# Ada.net
KiCad netlist of a schematic drawn in EasyEDA Pro
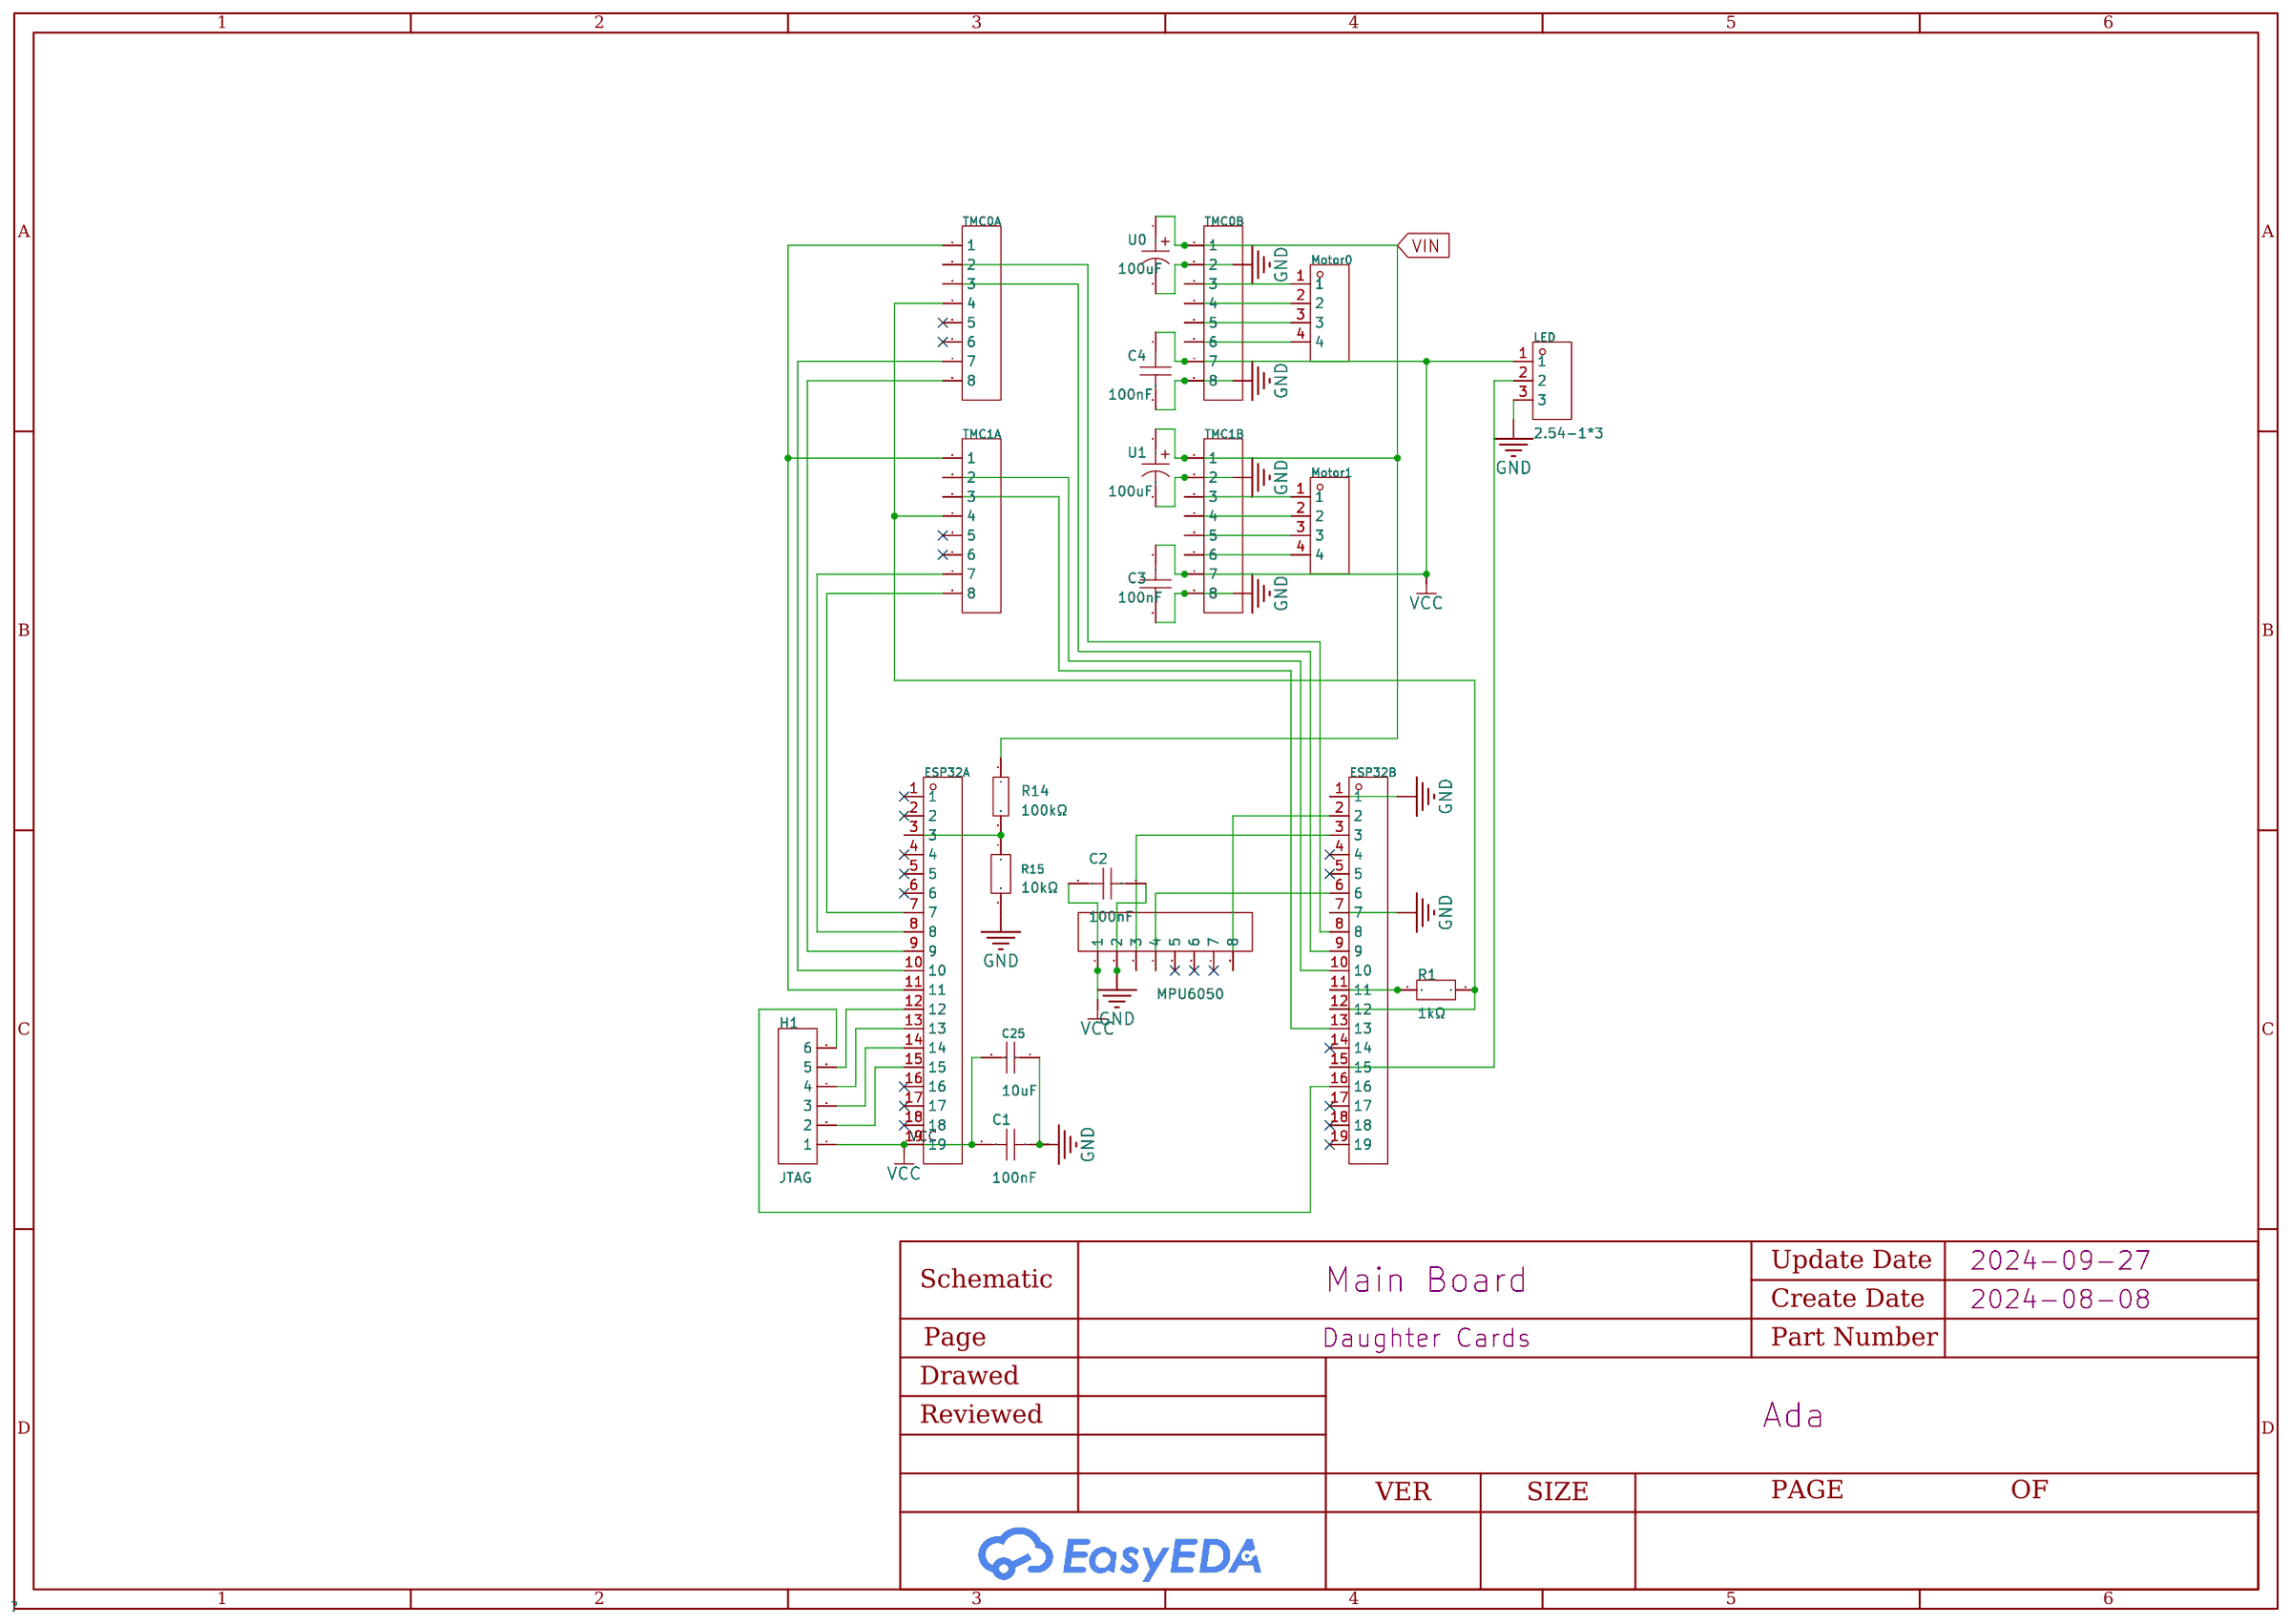
[diagram p0: Daughter Cards]
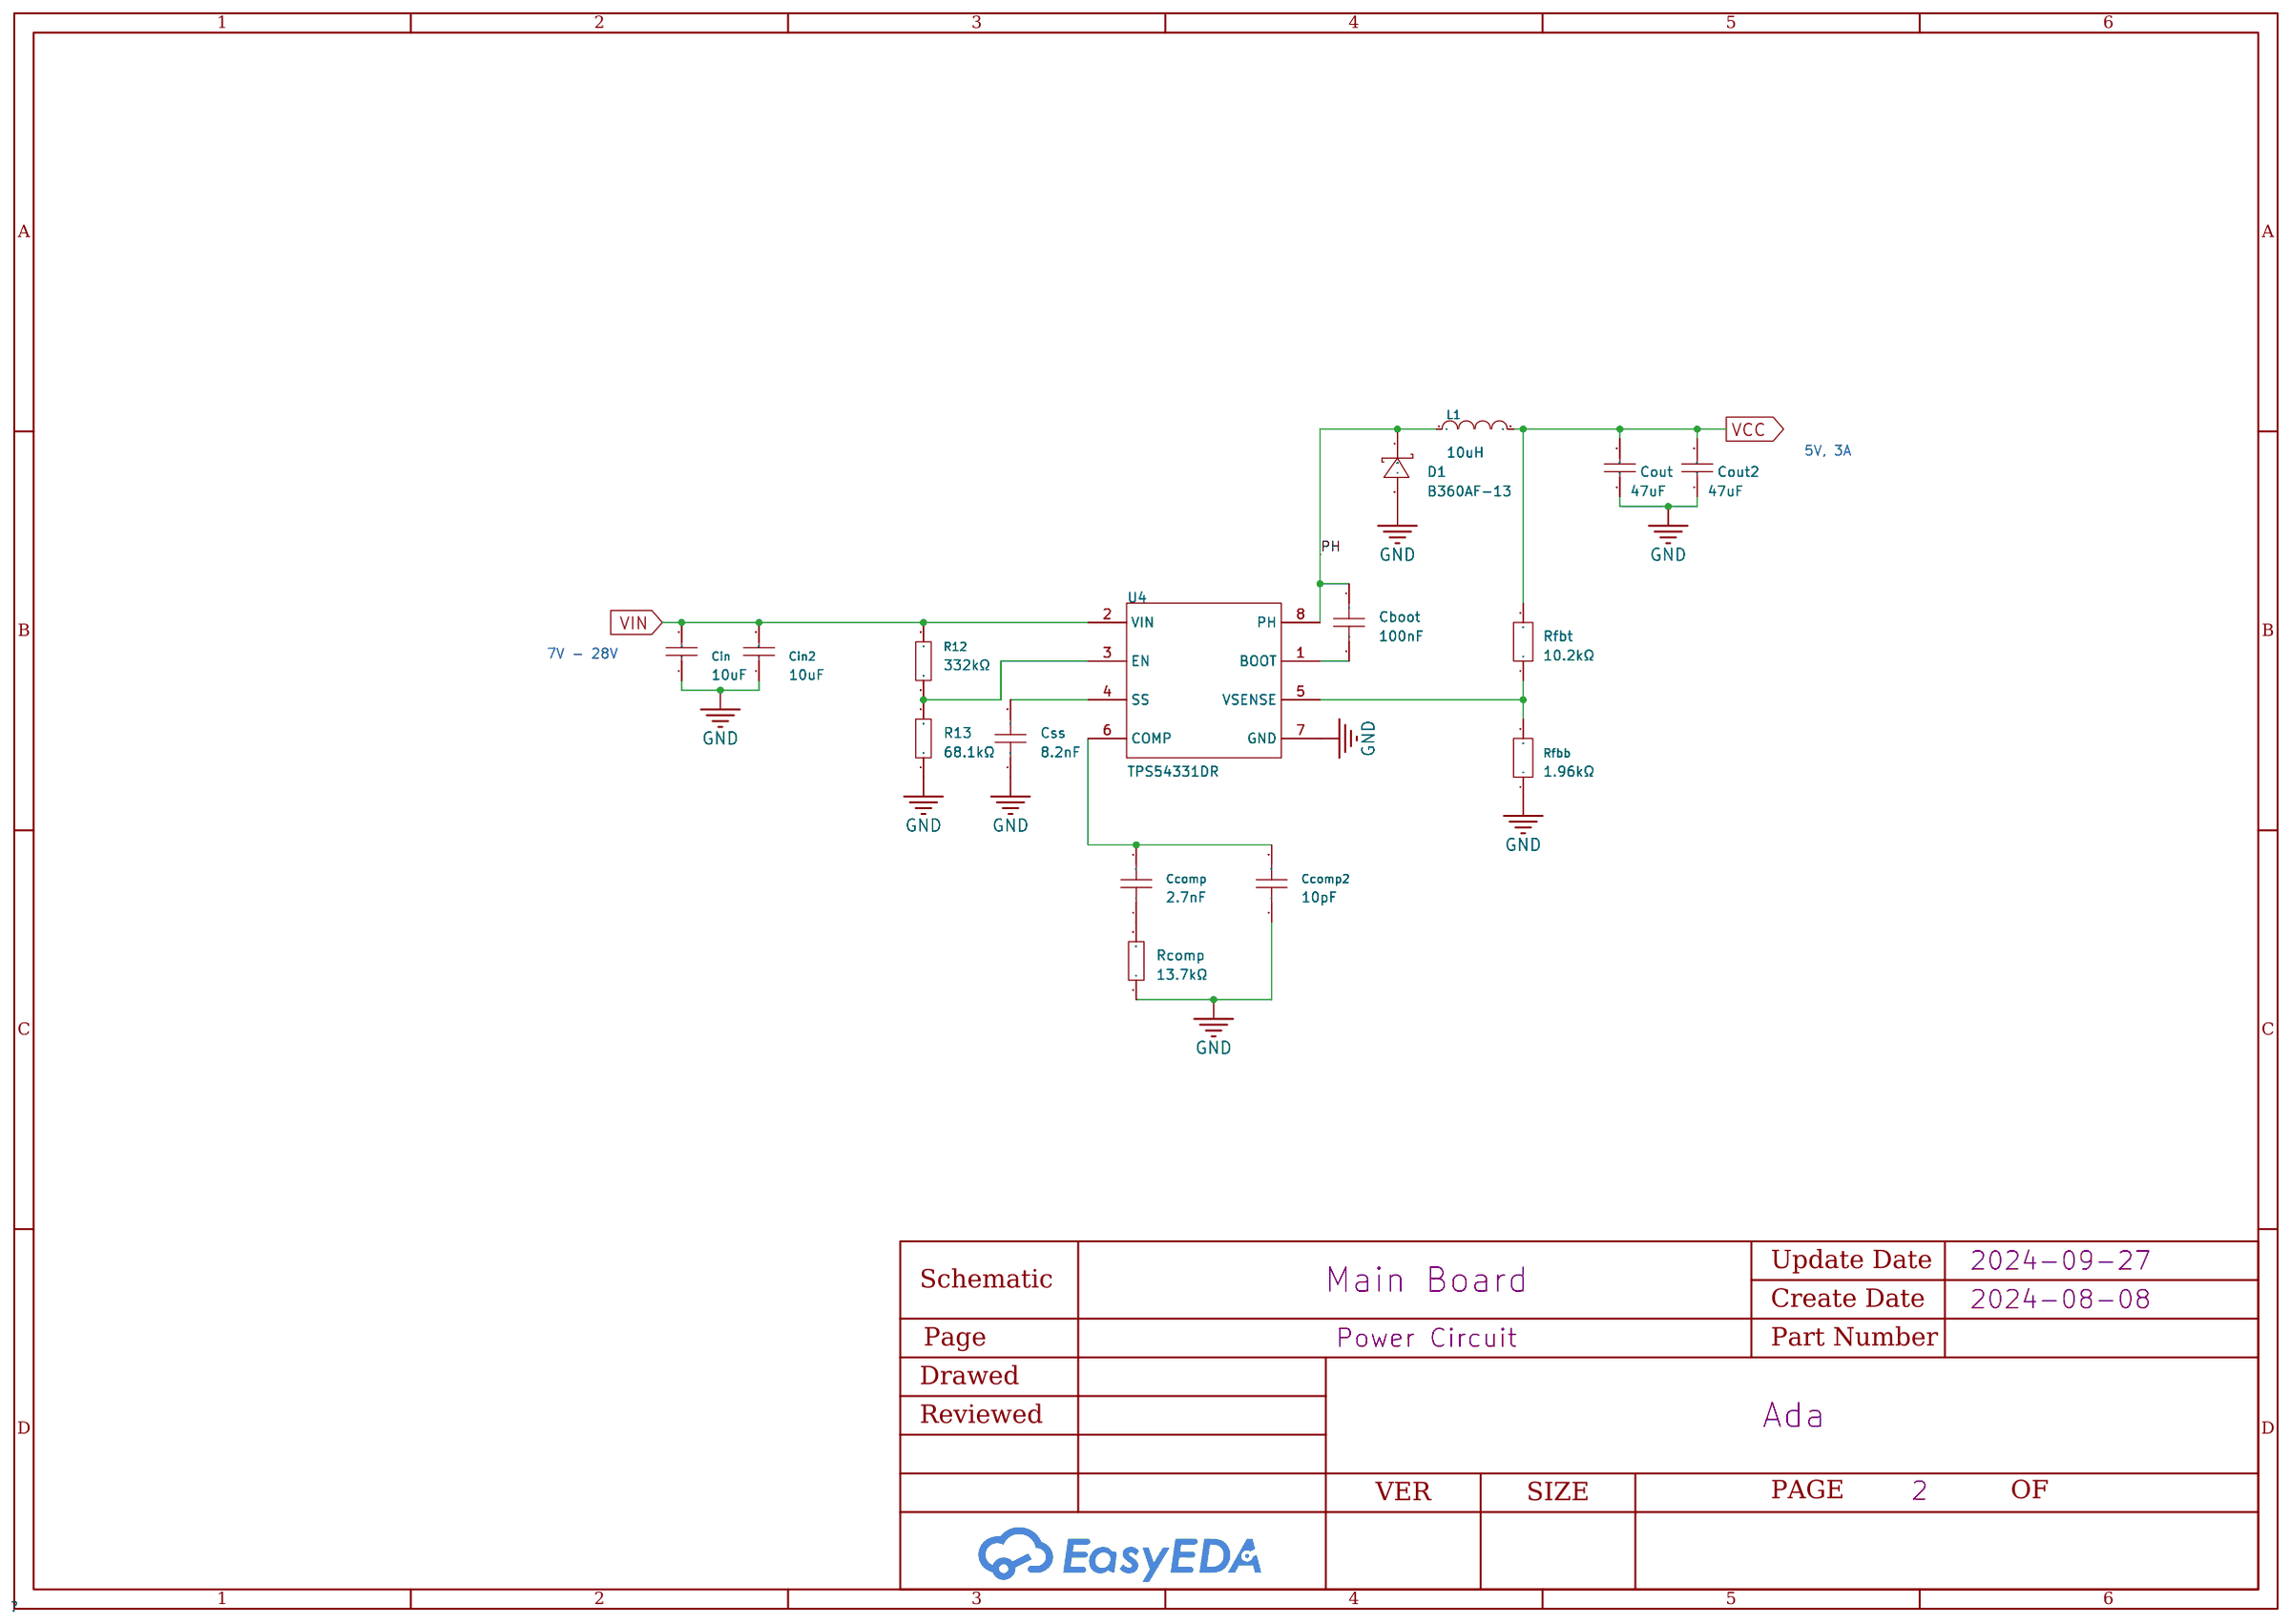
[diagram p1: Power Circuit]
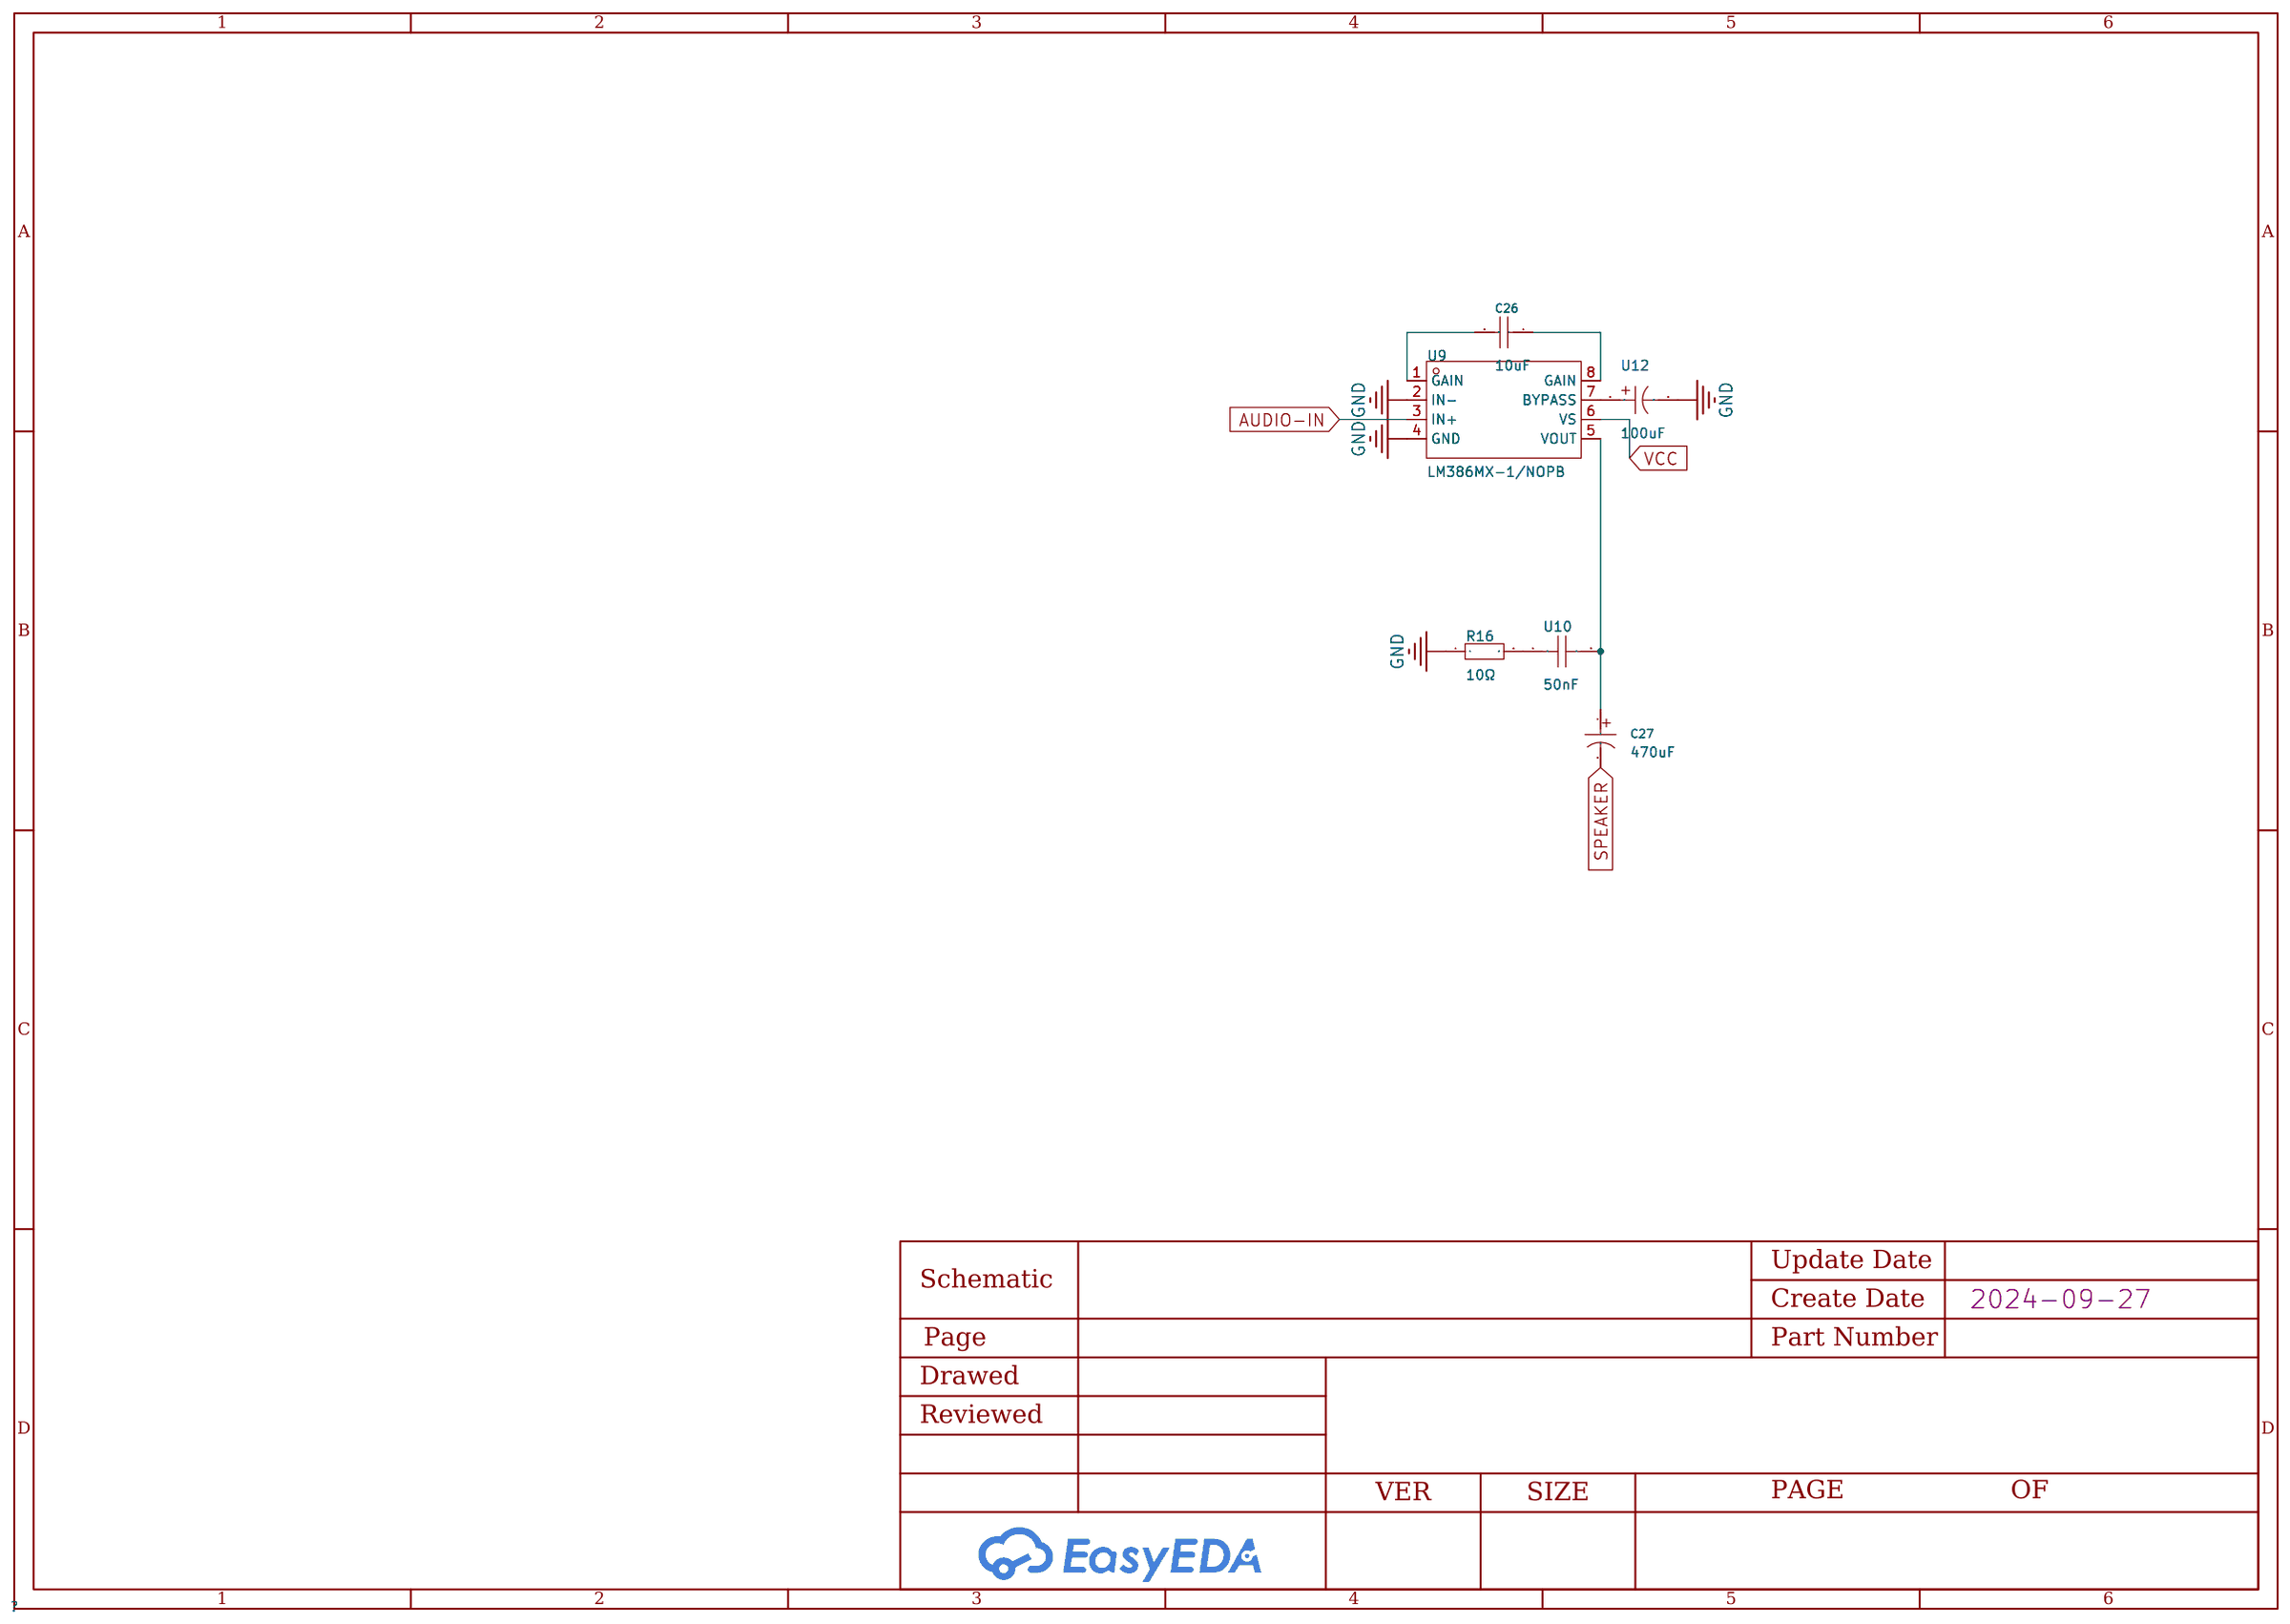
[diagram p2: Audio Amplifier]

(export (version "E")
  (design (tool "Eeschema 10.0.6"))
  (components
    (comp (ref "C1")
      (value "100nF")
      (footprint "easyedapro:C0201")
      (fields
        (field (name "Manufacturer Part") "CL03A104KQ3NNNC")
        (field (name "Manufacturer") "SAMSUNG(三星)")
      )
      (libsource (lib "easyedapro") (part "CL03A104KQ3NNNC"))
    )
    (comp (ref "C2")
      (value "100nF")
      (footprint "easyedapro:C0201")
      (fields
        (field (name "Manufacturer Part") "CL03A104KQ3NNNC")
        (field (name "Manufacturer") "SAMSUNG(三星)")
      )
      (libsource (lib "easyedapro") (part "CL03A104KQ3NNNC"))
    )
    (comp (ref "C3")
      (value "100nF")
      (footprint "easyedapro:C0201")
      (fields
        (field (name "Manufacturer Part") "CL03A104KQ3NNNC")
        (field (name "Manufacturer") "SAMSUNG(三星)")
      )
      (libsource (lib "easyedapro") (part "CL03A104KQ3NNNC"))
    )
    (comp (ref "C4")
      (value "100nF")
      (footprint "easyedapro:C0201")
      (fields
        (field (name "Manufacturer Part") "CL03A104KQ3NNNC")
        (field (name "Manufacturer") "SAMSUNG(三星)")
      )
      (libsource (lib "easyedapro") (part "CL03A104KQ3NNNC"))
    )
    (comp (ref "C25")
      (value "10uF")
      (footprint "easyedapro:C0402")
      (fields
        (field (name "Manufacturer Part") "CL05A106MQ5NUNC")
        (field (name "Manufacturer") "SAMSUNG(三星)")
      )
      (libsource (lib "easyedapro") (part "CL05A106MQ5NUNC"))
    )
    (comp (ref "ESP32A")
      (value "ESP32")
      (footprint "easyedapro:HDR-TH_19P-P2.54-V-F")
      (fields (field (name "Manufacturer Part") "2.54-1*19P母") (field (name "Manufacturer") "BOOMELE(博穆精密)"))
      (libsource (lib "easyedapro") (part "2.54-1*19P母"))
    )
    (comp (ref "ESP32B")
      (value "2.54-1*19P母")
      (footprint "easyedapro:HDR-TH_19P-P2.54-V-F")
      (fields (field (name "Manufacturer") "BOOMELE(博穆精密)"))
      (libsource (lib "easyedapro") (part "2.54-1*19P母"))
    )
    (comp (ref "H1")
      (value "JTAG")
      (footprint "easyedapro:HDR-TH_6P-P2.54-V-M-1")
      (fields (field (name "Manufacturer Part") "2.54-1x6P直针") (field (name "Manufacturer") "BOOMELE(博穆精密)"))
      (libsource (lib "easyedapro") (part "Header-Male-2.54_1x6"))
    )
    (comp (ref "LED")
      (value "2.54-1*3")
      (footprint "easyedapro:HDR-TH_3P-P2.54-V-M-1")
      (description "Pin Structure:1x3P Pitch:2.54mm Number of Rows:Plugin Number of Pins:3P Contact Plating:Gold")
      (fields (field (name "Manufacturer") "ZHOURI(洲日)"))
      (libsource (lib "easyedapro") (part "2.54-1*3"))
    )
    (comp (ref "Motor0")
      (value "Motor 0")
      (footprint "easyedapro:HDR-TH_4P-P2.54-V-M")
      (fields (field (name "Manufacturer Part") "PZ254V-11-04P") (field (name "Manufacturer") "XFCN(兴飞)"))
      (libsource (lib "easyedapro") (part "PZ254V-11-04P_C2691448"))
    )
    (comp (ref "Motor1")
      (value "Motor 1")
      (footprint "easyedapro:HDR-TH_4P-P2.54-V-M")
      (fields (field (name "Manufacturer Part") "PZ254V-11-04P") (field (name "Manufacturer") "XFCN(兴飞)"))
      (libsource (lib "easyedapro") (part "PZ254V-11-04P_C2691448"))
    )
    (comp (ref "MPU6050")
      (value "MPU6050")
      (footprint "easyedapro:HDR-TH_8P-P2.54-V-F-1")
      (fields (field (name "Manufacturer Part") "2.54-1*8P母环保") (field (name "Manufacturer") "BOOMELE(博穆精密)"))
      (libsource (lib "easyedapro") (part "Header-Female-2.54_1x8"))
    )
    (comp (ref "R1")
      (value "1kΩ")
      (footprint "easyedapro:R0603")
      (fields (field (name "Manufacturer Part") "FCR0603F1K") (field (name "Manufacturer") "VO(翔胜)"))
      (libsource (lib "easyedapro") (part "FCR0603F1K"))
    )
    (comp (ref "R14")
      (value "100kΩ")
      (footprint "easyedapro:R0201")
      (fields
        (field (name "Manufacturer Part") "0201WMF1003TEE")
        (field (name "Manufacturer") "UNI-ROYAL(厚声)")
      )
      (libsource (lib "easyedapro") (part "0201WMF1003TEE"))
    )
    (comp (ref "R15")
      (value "10kΩ")
      (footprint "easyedapro:R0201")
      (fields
        (field (name "Manufacturer Part") "0201WMF1002TEE")
        (field (name "Manufacturer") "UNI-ROYAL(厚声)")
      )
      (libsource (lib "easyedapro") (part "0201WMF1002TEE"))
    )
    (comp (ref "TMC0A")
      (value "TMC0A")
      (footprint "easyedapro:HDR-TH_8P-P2.54-V-F-1")
      (fields (field (name "Manufacturer Part") "2.54-1*8P母环保") (field (name "Manufacturer") "BOOMELE(博穆精密)"))
      (libsource (lib "easyedapro") (part "Header-Female-2.54_1x8"))
    )
    (comp (ref "TMC0B")
      (value "2.54-1*8P母环保")
      (footprint "easyedapro:HDR-TH_8P-P2.54-V-F-1")
      (fields (field (name "Manufacturer") "BOOMELE(博穆精密)"))
      (libsource (lib "easyedapro") (part "Header-Female-2.54_1x8"))
    )
    (comp (ref "TMC1A")
      (value "TMC2209")
      (footprint "easyedapro:HDR-TH_8P-P2.54-V-F-1")
      (fields (field (name "Manufacturer Part") "2.54-1*8P母环保") (field (name "Manufacturer") "BOOMELE(博穆精密)"))
      (libsource (lib "easyedapro") (part "Header-Female-2.54_1x8"))
    )
    (comp (ref "TMC1B")
      (value "2.54-1*8P母环保")
      (footprint "easyedapro:HDR-TH_8P-P2.54-V-F-1")
      (fields (field (name "Manufacturer") "BOOMELE(博穆精密)"))
      (libsource (lib "easyedapro") (part "Header-Female-2.54_1x8"))
    )
    (comp (ref "U0")
      (value "100uF")
      (footprint "easyedapro:CAP-TH_BD6.3-P2.50-D0.5-FD")
      (fields (field (name "Manufacturer Part") "03EC0728") (field (name "Manufacturer") "KNSCHA(科尼盛)"))
      (libsource (lib "easyedapro") (part "03EC0728"))
    )
    (comp (ref "U1")
      (value "100uF")
      (footprint "easyedapro:CAP-TH_BD6.3-P2.50-D0.5-FD")
      (fields (field (name "Manufacturer Part") "03EC0728") (field (name "Manufacturer") "KNSCHA(科尼盛)"))
      (libsource (lib "easyedapro") (part "03EC0728"))
    )
    (comp (ref "Cboot")
      (value "100nF")
      (footprint "easyedapro:C0201")
      (fields
        (field (name "Manufacturer Part") "CL03A104KQ3NNNC")
        (field (name "Manufacturer") "SAMSUNG(三星)")
      )
      (libsource (lib "easyedapro") (part "CL03A104KQ3NNNC"))
    )
    (comp (ref "Ccomp")
      (value "2.7nF")
      (footprint "easyedapro:C0402")
      (fields
        (field (name "Manufacturer Part") "CC0402KRX7R8BB272")
        (field (name "Manufacturer") "YAGEO(国巨)")
      )
      (libsource (lib "easyedapro") (part "CC0402KRX7R8BB272"))
    )
    (comp (ref "Ccomp2")
      (value "10pF")
      (footprint "easyedapro:C0402")
      (fields (field (name "Manufacturer Part") "0402N100J250CT") (field (name "Manufacturer") "Walsin(华新科)"))
      (libsource (lib "easyedapro") (part "0402N100J250CT"))
    )
    (comp (ref "Cin")
      (value "10uF")
      (footprint "easyedapro:C1206")
      (fields
        (field (name "Manufacturer Part") "CL31A106KAHNNNE")
        (field (name "Manufacturer") "SAMSUNG(三星)")
      )
      (libsource (lib "easyedapro") (part "CL31A106KAHNNNE"))
    )
    (comp (ref "Cin2")
      (value "10uF")
      (footprint "easyedapro:C1206")
      (fields
        (field (name "Manufacturer Part") "CL31A106KAHNNNE")
        (field (name "Manufacturer") "SAMSUNG(三星)")
      )
      (libsource (lib "easyedapro") (part "CL31A106KAHNNNE"))
    )
    (comp (ref "Cout")
      (value "47uF")
      (footprint "easyedapro:C0805")
      (fields
        (field (name "Manufacturer Part") "CL21A476MQYNNNE")
        (field (name "Manufacturer") "SAMSUNG(三星)")
      )
      (libsource (lib "easyedapro") (part "CL21A476MQYNNNE"))
    )
    (comp (ref "Cout2")
      (value "47uF")
      (footprint "easyedapro:C0805")
      (fields
        (field (name "Manufacturer Part") "CL21A476MQYNNNE")
        (field (name "Manufacturer") "SAMSUNG(三星)")
      )
      (libsource (lib "easyedapro") (part "CL21A476MQYNNNE"))
    )
    (comp (ref "Css")
      (value "8.2nF")
      (footprint "easyedapro:C0201")
      (fields (field (name "Manufacturer Part") "C0603X7R822KDTS") (field (name "Manufacturer") "DARFON(达方)"))
      (libsource (lib "easyedapro") (part "C0603X7R822KDTS"))
    )
    (comp (ref "D1")
      (value "B360AF-13")
      (footprint "easyedapro:SMA_L4.4-W2.6-LS5.0-RD")
      (fields (field (name "Manufacturer") "DIODES(美台)"))
      (libsource (lib "easyedapro") (part "B360AF-13"))
    )
    (comp (ref "L1")
      (value "10uH")
      (footprint "easyedapro:IND-SMD_L7.2-W6.6_GPSR07X0")
      (fields (field (name "Manufacturer Part") "CYA0630-10UH") (field (name "Manufacturer") "SHOU HAN(首韩)"))
      (libsource (lib "easyedapro") (part "CYA0630-10UH"))
    )
    (comp (ref "R12")
      (value "332kΩ")
      (footprint "easyedapro:R0402")
      (fields
        (field (name "Manufacturer Part") "0402WGF3323TCE")
        (field (name "Manufacturer") "UNI-ROYAL(厚声)")
      )
      (libsource (lib "easyedapro") (part "0402WGF3323TCE"))
    )
    (comp (ref "R13")
      (value "68.1kΩ")
      (footprint "easyedapro:R0402")
      (fields (field (name "Manufacturer Part") "AC0402FR-0768K1L") (field (name "Manufacturer") "YAGEO(国巨)"))
      (libsource (lib "easyedapro") (part "AC0402FR-0768K1L"))
    )
    (comp (ref "Rcomp")
      (value "13.7kΩ")
      (footprint "easyedapro:R0201")
      (fields (field (name "Manufacturer Part") "RC-01W1372FT") (field (name "Manufacturer") "FH(风华)"))
      (libsource (lib "easyedapro") (part "RC-01W1372FT"))
    )
    (comp (ref "Rfbb")
      (value "1.96kΩ")
      (footprint "easyedapro:R0201")
      (fields
        (field (name "Manufacturer Part") "0201WMF1961TEE")
        (field (name "Manufacturer") "UNI-ROYAL(厚声)")
      )
      (libsource (lib "easyedapro") (part "0201WMF1961TEE"))
    )
    (comp (ref "Rfbt")
      (value "10.2kΩ")
      (footprint "easyedapro:R0201")
      (fields (field (name "Manufacturer Part") "RTT011022FTH") (field (name "Manufacturer") "RALEC(旺诠)"))
      (libsource (lib "easyedapro") (part "RTT011022FTH"))
    )
    (comp (ref "U4")
      (value "TPS54331DR")
      (footprint "easyedapro:SOIC-8_L5.0-W4.0-P1.27-LS6.0-BL")
      (fields (field (name "Manufacturer") "TI(德州仪器)"))
      (libsource (lib "easyedapro") (part "TPS54331DR"))
    )
    (comp (ref "C26")
      (value "10uF")
      (footprint "easyedapro:C0402")
      (fields
        (field (name "Manufacturer Part") "CL05A106MQ5NUNC")
        (field (name "Manufacturer") "SAMSUNG(三星)")
      )
      (libsource (lib "easyedapro") (part "CL05A106MQ5NUNC"))
    )
    (comp (ref "C27")
      (value "470uF")
      (footprint "easyedapro:CAP-TH_BD8.0-P3.50-D0.6-FD")
      (fields
        (field (name "Manufacturer Part") "KM477M016F12RR0VH2FP0")
        (field (name "Manufacturer") "CX(承兴)")
      )
      (libsource (lib "easyedapro") (part "470uf16v"))
    )
    (comp (ref "R16")
      (value "10Ω")
      (footprint "easyedapro:R01005")
      (fields (field (name "Manufacturer Part") "MCR004YZPJ100") (field (name "Manufacturer") "ROHM(罗姆)"))
      (libsource (lib "easyedapro") (part "MCR004YZPJ100"))
    )
    (comp (ref "U9")
      (value "LM386MX-1/NOPB")
      (footprint "easyedapro:SOIC-8_L4.9-W3.9-P1.27-LS6.0-BL")
      (fields (field (name "Manufacturer") "TI(德州仪器)"))
      (libsource (lib "easyedapro") (part "LM386MX-1/NOPB"))
    )
    (comp (ref "U10")
      (value "50nF")
      (footprint "easyedapro:C1206")
      (fields (field (name "Manufacturer Part") "12065C503JAT2A") (field (name "Manufacturer") "Kyocera AVX"))
      (libsource (lib "easyedapro") (part "12065C503JAT2A"))
    )
    (comp (ref "U12")
      (value "100uF")
      (footprint "easyedapro:CAP-TH_BD6.3-P2.50-D0.5-FD")
      (fields (field (name "Manufacturer Part") "03EC0728") (field (name "Manufacturer") "KNSCHA(科尼盛)"))
      (libsource (lib "easyedapro") (part "03EC0728"))
    )
  )
  (nets
    (net (code "1") (name "AUDIO-IN") (class "Default")
      (node (ref "U9") (pin "3") (pinfunction "IN+_3") (pintype "input"))
    )
    (net (code "2") (name "GND") (class "Default")
      (node (ref "C1") (pin "2") (pinfunction "2_2") (pintype "unspecified"))
      (node (ref "C2") (pin "2") (pinfunction "2_2") (pintype "unspecified"))
      (node (ref "C25") (pin "1") (pinfunction "1_1") (pintype "input"))
      (node (ref "C3") (pin "2") (pinfunction "2_2") (pintype "unspecified"))
      (node (ref "C4") (pin "2") (pinfunction "2_2") (pintype "unspecified"))
      (node (ref "Ccomp2") (pin "1") (pinfunction "1_1") (pintype "input"))
      (node (ref "Cin") (pin "1") (pinfunction "1_1") (pintype "input"))
      (node (ref "Cin2") (pin "1") (pinfunction "1_1") (pintype "input"))
      (node (ref "Cout") (pin "1") (pinfunction "1_1") (pintype "input"))
      (node (ref "Cout2") (pin "1") (pinfunction "1_1") (pintype "input"))
      (node (ref "Css") (pin "1") (pinfunction "1_1") (pintype "unspecified"))
      (node (ref "D1") (pin "2") (pinfunction "A_2") (pintype "unspecified"))
      (node (ref "ESP32B") (pin "1") (pinfunction "1_1") (pintype "input"))
      (node (ref "ESP32B") (pin "7") (pinfunction "7_7") (pintype "input"))
      (node (ref "LED") (pin "3") (pinfunction "3_3") (pintype "input"))
      (node (ref "MPU6050") (pin "2") (pinfunction "2_2") (pintype "input"))
      (node (ref "R13") (pin "1") (pinfunction "1_1") (pintype "unspecified"))
      (node (ref "R15") (pin "2") (pinfunction "2_2") (pintype "input"))
      (node (ref "R16") (pin "1") (pinfunction "1_1") (pintype "input"))
      (node (ref "Rcomp") (pin "1") (pinfunction "1_1") (pintype "unspecified"))
      (node (ref "Rfbb") (pin "1") (pinfunction "1_1") (pintype "input"))
      (node (ref "TMC0B") (pin "2") (pinfunction "2_2") (pintype "input"))
      (node (ref "TMC0B") (pin "8") (pinfunction "8_8") (pintype "input"))
      (node (ref "TMC1B") (pin "2") (pinfunction "2_2") (pintype "input"))
      (node (ref "TMC1B") (pin "8") (pinfunction "8_8") (pintype "input"))
      (node (ref "U0") (pin "2") (pinfunction "2_2") (pintype "input"))
      (node (ref "U1") (pin "2") (pinfunction "2_2") (pintype "input"))
      (node (ref "U12") (pin "2") (pinfunction "2_2") (pintype "input"))
      (node (ref "U4") (pin "7") (pinfunction "GND_7") (pintype "unspecified"))
      (node (ref "U9") (pin "2") (pinfunction "IN-_2") (pintype "input"))
      (node (ref "U9") (pin "4") (pinfunction "GND_4") (pintype "input"))
    )
    (net (code "3") (name "Net-(C26-Pad1)") (class "Default")
      (node (ref "C26") (pin "1") (pinfunction "1_1") (pintype "input"))
      (node (ref "U9") (pin "8") (pinfunction "GAIN_8") (pintype "input"))
    )
    (net (code "4") (name "Net-(C26-Pad2)") (class "Default")
      (node (ref "C26") (pin "2") (pinfunction "2_2") (pintype "input"))
      (node (ref "U9") (pin "1") (pinfunction "GAIN_1") (pintype "input"))
    )
    (net (code "5") (name "Net-(Ccomp-Pad1)") (class "Default")
      (node (ref "Ccomp") (pin "1") (pinfunction "1_1") (pintype "input"))
      (node (ref "Rcomp") (pin "2") (pinfunction "2_2") (pintype "unspecified"))
    )
    (net (code "6") (name "Net-(ESP32A-Pad3)") (class "Default")
      (node (ref "ESP32A") (pin "3") (pinfunction "3_3") (pintype "input"))
      (node (ref "R14") (pin "2") (pinfunction "2_2") (pintype "unspecified"))
      (node (ref "R15") (pin "1") (pinfunction "1_1") (pintype "input"))
    )
    (net (code "7") (name "Net-(ESP32A-Pad7)") (class "Default")
      (node (ref "ESP32A") (pin "7") (pinfunction "7_7") (pintype "input"))
      (node (ref "TMC1A") (pin "8") (pinfunction "8_8") (pintype "input"))
    )
    (net (code "8") (name "Net-(ESP32A-Pad8)") (class "Default")
      (node (ref "ESP32A") (pin "8") (pinfunction "8_8") (pintype "input"))
      (node (ref "TMC1A") (pin "7") (pinfunction "7_7") (pintype "input"))
    )
    (net (code "9") (name "Net-(ESP32A-Pad9)") (class "Default")
      (node (ref "ESP32A") (pin "9") (pinfunction "9_9") (pintype "input"))
      (node (ref "TMC0A") (pin "8") (pinfunction "8_8") (pintype "input"))
    )
    (net (code "10") (name "Net-(ESP32A-Pad10)") (class "Default")
      (node (ref "ESP32A") (pin "10") (pinfunction "10_10") (pintype "input"))
      (node (ref "TMC0A") (pin "7") (pinfunction "7_7") (pintype "input"))
    )
    (net (code "11") (name "Net-(ESP32A-Pad11)") (class "Default")
      (node (ref "ESP32A") (pin "11") (pinfunction "11_11") (pintype "input"))
      (node (ref "TMC0A") (pin "1") (pinfunction "1_1") (pintype "input"))
      (node (ref "TMC1A") (pin "1") (pinfunction "1_1") (pintype "input"))
    )
    (net (code "12") (name "Net-(ESP32A-Pad12)") (class "Default")
      (node (ref "ESP32A") (pin "12") (pinfunction "12_12") (pintype "input"))
      (node (ref "H1") (pin "5") (pinfunction "5_5") (pintype "input"))
    )
    (net (code "13") (name "Net-(ESP32A-Pad13)") (class "Default")
      (node (ref "ESP32A") (pin "13") (pinfunction "13_13") (pintype "input"))
      (node (ref "H1") (pin "4") (pinfunction "4_4") (pintype "input"))
    )
    (net (code "14") (name "Net-(ESP32A-Pad14)") (class "Default")
      (node (ref "ESP32A") (pin "14") (pinfunction "14_14") (pintype "input"))
      (node (ref "H1") (pin "3") (pinfunction "3_3") (pintype "input"))
    )
    (net (code "15") (name "Net-(ESP32A-Pad15)") (class "Default")
      (node (ref "ESP32A") (pin "15") (pinfunction "15_15") (pintype "input"))
      (node (ref "H1") (pin "2") (pinfunction "2_2") (pintype "input"))
    )
    (net (code "16") (name "Net-(ESP32B-Pad2)") (class "Default")
      (node (ref "ESP32B") (pin "2") (pinfunction "2_2") (pintype "input"))
      (node (ref "MPU6050") (pin "8") (pinfunction "8_8") (pintype "input"))
    )
    (net (code "17") (name "Net-(ESP32B-Pad3)") (class "Default")
      (node (ref "ESP32B") (pin "3") (pinfunction "3_3") (pintype "input"))
      (node (ref "MPU6050") (pin "3") (pinfunction "3_3") (pintype "input"))
    )
    (net (code "18") (name "Net-(ESP32B-Pad6)") (class "Default")
      (node (ref "ESP32B") (pin "6") (pinfunction "6_6") (pintype "input"))
      (node (ref "MPU6050") (pin "4") (pinfunction "4_4") (pintype "input"))
    )
    (net (code "19") (name "Net-(ESP32B-Pad8)") (class "Default")
      (node (ref "ESP32B") (pin "8") (pinfunction "8_8") (pintype "input"))
      (node (ref "TMC0A") (pin "2") (pinfunction "2_2") (pintype "input"))
    )
    (net (code "20") (name "Net-(ESP32B-Pad9)") (class "Default")
      (node (ref "ESP32B") (pin "9") (pinfunction "9_9") (pintype "input"))
      (node (ref "TMC0A") (pin "3") (pinfunction "3_3") (pintype "input"))
    )
    (net (code "21") (name "Net-(ESP32B-Pad10)") (class "Default")
      (node (ref "ESP32B") (pin "10") (pinfunction "10_10") (pintype "input"))
      (node (ref "TMC1A") (pin "2") (pinfunction "2_2") (pintype "input"))
    )
    (net (code "22") (name "Net-(ESP32B-Pad11)") (class "Default")
      (node (ref "ESP32B") (pin "11") (pinfunction "11_11") (pintype "input"))
      (node (ref "R1") (pin "1") (pinfunction "1_1") (pintype "unspecified"))
    )
    (net (code "23") (name "Net-(ESP32B-Pad12)") (class "Default")
      (node (ref "ESP32B") (pin "12") (pinfunction "12_12") (pintype "input"))
      (node (ref "R1") (pin "2") (pinfunction "2_2") (pintype "unspecified"))
      (node (ref "TMC0A") (pin "4") (pinfunction "4_4") (pintype "input"))
      (node (ref "TMC1A") (pin "4") (pinfunction "4_4") (pintype "input"))
    )
    (net (code "24") (name "Net-(ESP32B-Pad13)") (class "Default")
      (node (ref "ESP32B") (pin "13") (pinfunction "13_13") (pintype "input"))
      (node (ref "TMC1A") (pin "3") (pinfunction "3_3") (pintype "input"))
    )
    (net (code "25") (name "Net-(ESP32B-Pad15)") (class "Default")
      (node (ref "ESP32B") (pin "15") (pinfunction "15_15") (pintype "input"))
      (node (ref "LED") (pin "2") (pinfunction "2_2") (pintype "input"))
    )
    (net (code "26") (name "Net-(ESP32B-Pad16)") (class "Default")
      (node (ref "ESP32B") (pin "16") (pinfunction "16_16") (pintype "input"))
      (node (ref "H1") (pin "6") (pinfunction "6_6") (pintype "input"))
    )
    (net (code "27") (name "Net-(Motor0-Pad1)") (class "Default")
      (node (ref "Motor0") (pin "1") (pinfunction "1_1") (pintype "input"))
      (node (ref "TMC0B") (pin "3") (pinfunction "3_3") (pintype "input"))
    )
    (net (code "28") (name "Net-(Motor0-Pad2)") (class "Default")
      (node (ref "Motor0") (pin "2") (pinfunction "2_2") (pintype "input"))
      (node (ref "TMC0B") (pin "4") (pinfunction "4_4") (pintype "input"))
    )
    (net (code "29") (name "Net-(Motor0-Pad3)") (class "Default")
      (node (ref "Motor0") (pin "3") (pinfunction "3_3") (pintype "input"))
      (node (ref "TMC0B") (pin "5") (pinfunction "5_5") (pintype "input"))
    )
    (net (code "30") (name "Net-(Motor0-Pad4)") (class "Default")
      (node (ref "Motor0") (pin "4") (pinfunction "4_4") (pintype "input"))
      (node (ref "TMC0B") (pin "6") (pinfunction "6_6") (pintype "input"))
    )
    (net (code "31") (name "Net-(Motor1-Pad1)") (class "Default")
      (node (ref "Motor1") (pin "1") (pinfunction "1_1") (pintype "input"))
      (node (ref "TMC1B") (pin "3") (pinfunction "3_3") (pintype "input"))
    )
    (net (code "32") (name "Net-(Motor1-Pad2)") (class "Default")
      (node (ref "Motor1") (pin "2") (pinfunction "2_2") (pintype "input"))
      (node (ref "TMC1B") (pin "4") (pinfunction "4_4") (pintype "input"))
    )
    (net (code "33") (name "Net-(Motor1-Pad3)") (class "Default")
      (node (ref "Motor1") (pin "3") (pinfunction "3_3") (pintype "input"))
      (node (ref "TMC1B") (pin "5") (pinfunction "5_5") (pintype "input"))
    )
    (net (code "34") (name "Net-(Motor1-Pad4)") (class "Default")
      (node (ref "Motor1") (pin "4") (pinfunction "4_4") (pintype "input"))
      (node (ref "TMC1B") (pin "6") (pinfunction "6_6") (pintype "input"))
    )
    (net (code "35") (name "Net-(R16-Pad2)") (class "Default")
      (node (ref "R16") (pin "2") (pinfunction "2_2") (pintype "input"))
      (node (ref "U10") (pin "1") (pinfunction "1_1") (pintype "input"))
    )
    (net (code "36") (name "Net-(U4-BOOT)") (class "Default")
      (node (ref "Cboot") (pin "2") (pinfunction "2_2") (pintype "unspecified"))
      (node (ref "U4") (pin "1") (pinfunction "BOOT_1") (pintype "unspecified"))
    )
    (net (code "37") (name "Net-(U4-COMP)") (class "Default")
      (node (ref "Ccomp") (pin "2") (pinfunction "2_2") (pintype "input"))
      (node (ref "Ccomp2") (pin "2") (pinfunction "2_2") (pintype "input"))
      (node (ref "U4") (pin "6") (pinfunction "COMP_6") (pintype "unspecified"))
    )
    (net (code "38") (name "Net-(U4-EN)") (class "Default")
      (node (ref "R12") (pin "1") (pinfunction "1_1") (pintype "input"))
      (node (ref "R13") (pin "2") (pinfunction "2_2") (pintype "unspecified"))
      (node (ref "U4") (pin "3") (pinfunction "EN_3") (pintype "unspecified"))
    )
    (net (code "39") (name "Net-(U4-SS)") (class "Default")
      (node (ref "Css") (pin "2") (pinfunction "2_2") (pintype "unspecified"))
      (node (ref "U4") (pin "4") (pinfunction "SS_4") (pintype "unspecified"))
    )
    (net (code "40") (name "Net-(U4-VSENSE)") (class "Default")
      (node (ref "Rfbb") (pin "2") (pinfunction "2_2") (pintype "input"))
      (node (ref "Rfbt") (pin "1") (pinfunction "1_1") (pintype "unspecified"))
      (node (ref "U4") (pin "5") (pinfunction "VSENSE_5") (pintype "unspecified"))
    )
    (net (code "41") (name "Net-(U9-BYPASS)") (class "Default")
      (node (ref "U12") (pin "1") (pinfunction "1_1") (pintype "input"))
      (node (ref "U9") (pin "7") (pinfunction "BYPASS_7") (pintype "input"))
    )
    (net (code "42") (name "Net-(U9-VOUT)") (class "Default")
      (node (ref "C27") (pin "1") (pinfunction "1_1") (pintype "input"))
      (node (ref "U10") (pin "2") (pinfunction "2_2") (pintype "input"))
      (node (ref "U9") (pin "5") (pinfunction "VOUT_5") (pintype "input"))
    )
    (net (code "43") (name "PH") (class "Default")
      (node (ref "Cboot") (pin "1") (pinfunction "1_1") (pintype "unspecified"))
      (node (ref "D1") (pin "1") (pinfunction "C_1") (pintype "unspecified"))
      (node (ref "L1") (pin "1") (pinfunction "1_1") (pintype "input"))
      (node (ref "U4") (pin "8") (pinfunction "PH_8") (pintype "unspecified"))
    )
    (net (code "44") (name "SPEAKER") (class "Default")
      (node (ref "C27") (pin "2") (pinfunction "2_2") (pintype "input"))
    )
    (net (code "45") (name "VCC") (class "Default")
      (node (ref "C1") (pin "1") (pinfunction "1_1") (pintype "unspecified"))
      (node (ref "C2") (pin "1") (pinfunction "1_1") (pintype "unspecified"))
      (node (ref "C25") (pin "2") (pinfunction "2_2") (pintype "input"))
      (node (ref "C3") (pin "1") (pinfunction "1_1") (pintype "unspecified"))
      (node (ref "C4") (pin "1") (pinfunction "1_1") (pintype "unspecified"))
      (node (ref "Cout") (pin "2") (pinfunction "2_2") (pintype "input"))
      (node (ref "Cout2") (pin "2") (pinfunction "2_2") (pintype "input"))
      (node (ref "ESP32A") (pin "19") (pinfunction "19_19") (pintype "input"))
      (node (ref "H1") (pin "1") (pinfunction "1_1") (pintype "input"))
      (node (ref "L1") (pin "2") (pinfunction "2_2") (pintype "input"))
      (node (ref "LED") (pin "1") (pinfunction "1_1") (pintype "input"))
      (node (ref "MPU6050") (pin "1") (pinfunction "1_1") (pintype "input"))
      (node (ref "Rfbt") (pin "2") (pinfunction "2_2") (pintype "unspecified"))
      (node (ref "TMC0B") (pin "7") (pinfunction "7_7") (pintype "input"))
      (node (ref "TMC1B") (pin "7") (pinfunction "7_7") (pintype "input"))
      (node (ref "U9") (pin "6") (pinfunction "VS_6") (pintype "input"))
    )
    (net (code "46") (name "VIN") (class "Default")
      (node (ref "Cin") (pin "2") (pinfunction "2_2") (pintype "input"))
      (node (ref "Cin2") (pin "2") (pinfunction "2_2") (pintype "input"))
      (node (ref "R12") (pin "2") (pinfunction "2_2") (pintype "input"))
      (node (ref "R14") (pin "1") (pinfunction "1_1") (pintype "unspecified"))
      (node (ref "TMC0B") (pin "1") (pinfunction "1_1") (pintype "input"))
      (node (ref "TMC1B") (pin "1") (pinfunction "1_1") (pintype "input"))
      (node (ref "U0") (pin "1") (pinfunction "1_1") (pintype "input"))
      (node (ref "U1") (pin "1") (pinfunction "1_1") (pintype "input"))
      (node (ref "U4") (pin "2") (pinfunction "VIN_2") (pintype "unspecified"))
    )
    (net (code "47") (name "unconnected-(ESP32A-Pad1)") (class "Default")
      (node (ref "ESP32A") (pin "1") (pinfunction "1_1") (pintype "input+no_connect"))
    )
    (net (code "48") (name "unconnected-(ESP32A-Pad2)") (class "Default")
      (node (ref "ESP32A") (pin "2") (pinfunction "2_2") (pintype "input+no_connect"))
    )
    (net (code "49") (name "unconnected-(ESP32A-Pad4)") (class "Default")
      (node (ref "ESP32A") (pin "4") (pinfunction "4_4") (pintype "input+no_connect"))
    )
    (net (code "50") (name "unconnected-(ESP32A-Pad5)") (class "Default")
      (node (ref "ESP32A") (pin "5") (pinfunction "5_5") (pintype "input+no_connect"))
    )
    (net (code "51") (name "unconnected-(ESP32A-Pad6)") (class "Default")
      (node (ref "ESP32A") (pin "6") (pinfunction "6_6") (pintype "input+no_connect"))
    )
    (net (code "52") (name "unconnected-(ESP32A-Pad16)") (class "Default")
      (node (ref "ESP32A") (pin "16") (pinfunction "16_16") (pintype "input+no_connect"))
    )
    (net (code "53") (name "unconnected-(ESP32A-Pad17)") (class "Default")
      (node (ref "ESP32A") (pin "17") (pinfunction "17_17") (pintype "input+no_connect"))
    )
    (net (code "54") (name "unconnected-(ESP32A-Pad18)") (class "Default")
      (node (ref "ESP32A") (pin "18") (pinfunction "18_18") (pintype "input+no_connect"))
    )
    (net (code "55") (name "unconnected-(ESP32B-Pad4)") (class "Default")
      (node (ref "ESP32B") (pin "4") (pinfunction "4_4") (pintype "input+no_connect"))
    )
    (net (code "56") (name "unconnected-(ESP32B-Pad5)") (class "Default")
      (node (ref "ESP32B") (pin "5") (pinfunction "5_5") (pintype "input+no_connect"))
    )
    (net (code "57") (name "unconnected-(ESP32B-Pad14)") (class "Default")
      (node (ref "ESP32B") (pin "14") (pinfunction "14_14") (pintype "input+no_connect"))
    )
    (net (code "58") (name "unconnected-(ESP32B-Pad17)") (class "Default")
      (node (ref "ESP32B") (pin "17") (pinfunction "17_17") (pintype "input+no_connect"))
    )
    (net (code "59") (name "unconnected-(ESP32B-Pad18)") (class "Default")
      (node (ref "ESP32B") (pin "18") (pinfunction "18_18") (pintype "input+no_connect"))
    )
    (net (code "60") (name "unconnected-(ESP32B-Pad19)") (class "Default")
      (node (ref "ESP32B") (pin "19") (pinfunction "19_19") (pintype "input+no_connect"))
    )
    (net (code "61") (name "unconnected-(MPU6050-Pad5)") (class "Default")
      (node (ref "MPU6050") (pin "5") (pinfunction "5_5") (pintype "input+no_connect"))
    )
    (net (code "62") (name "unconnected-(MPU6050-Pad6)") (class "Default")
      (node (ref "MPU6050") (pin "6") (pinfunction "6_6") (pintype "input+no_connect"))
    )
    (net (code "63") (name "unconnected-(MPU6050-Pad7)") (class "Default")
      (node (ref "MPU6050") (pin "7") (pinfunction "7_7") (pintype "input+no_connect"))
    )
    (net (code "64") (name "unconnected-(TMC0A-Pad5)") (class "Default")
      (node (ref "TMC0A") (pin "5") (pinfunction "5_5") (pintype "input+no_connect"))
    )
    (net (code "65") (name "unconnected-(TMC0A-Pad6)") (class "Default")
      (node (ref "TMC0A") (pin "6") (pinfunction "6_6") (pintype "input+no_connect"))
    )
    (net (code "66") (name "unconnected-(TMC1A-Pad5)") (class "Default")
      (node (ref "TMC1A") (pin "5") (pinfunction "5_5") (pintype "input+no_connect"))
    )
    (net (code "67") (name "unconnected-(TMC1A-Pad6)") (class "Default")
      (node (ref "TMC1A") (pin "6") (pinfunction "6_6") (pintype "input+no_connect"))
    )
  )
)
